# VoxPopuli.net
KiCad netlist of a schematic drawn in Altium Designer
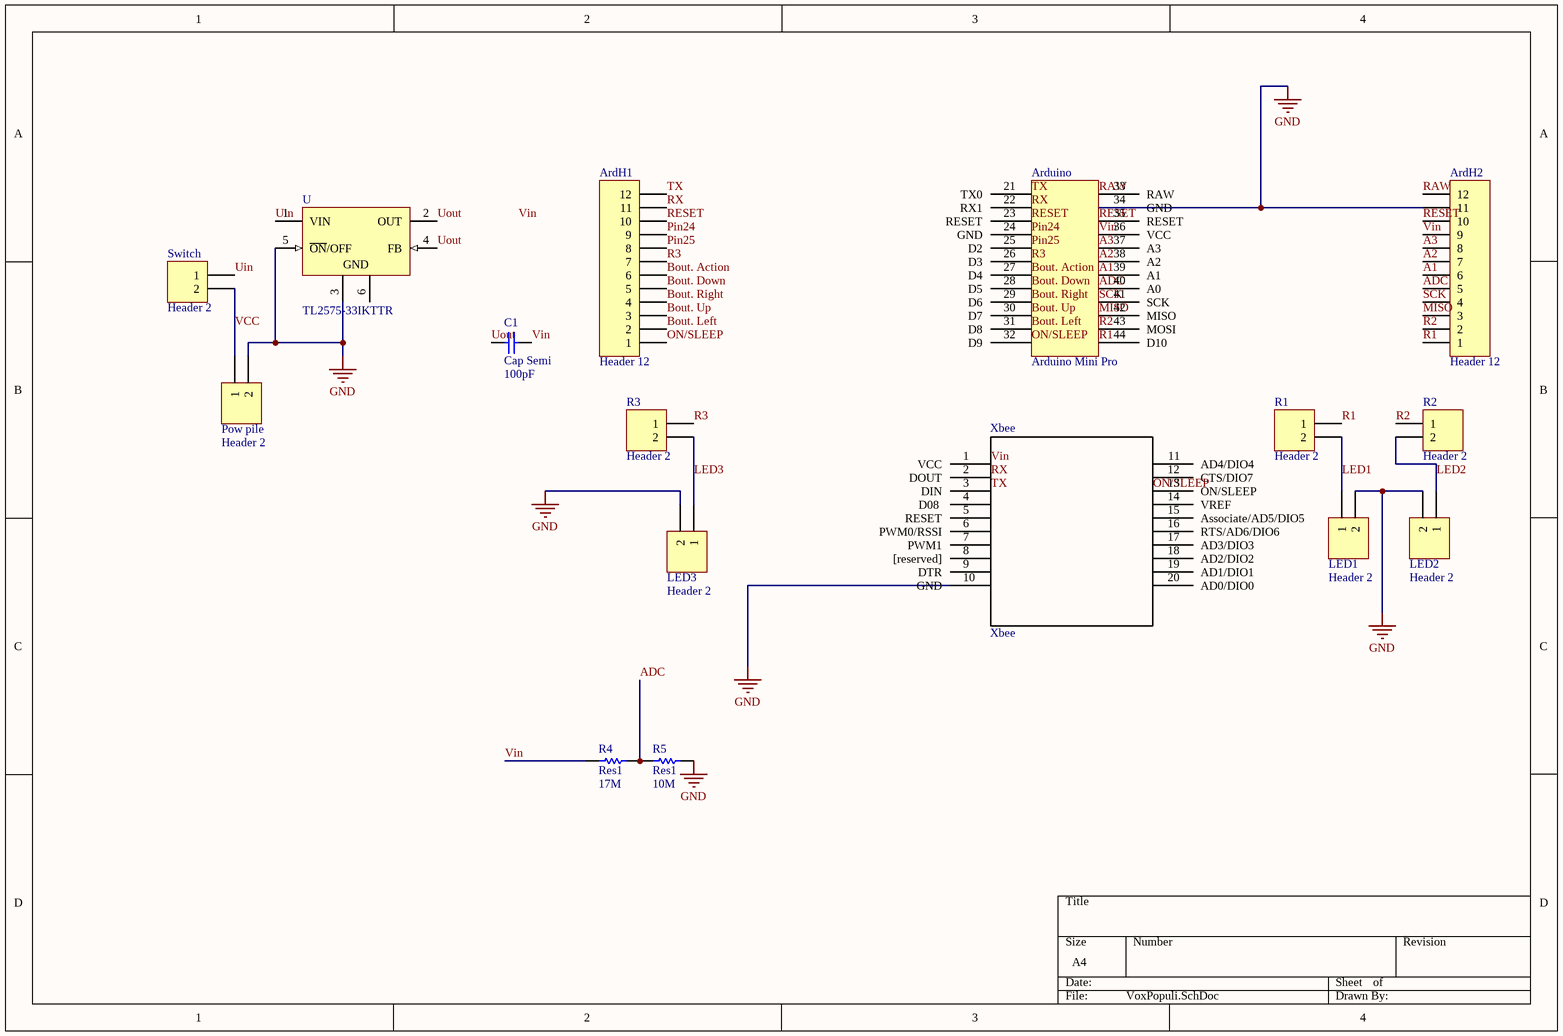
[diagram p0: VoxPopuli.SchDoc]

(export (version "E")
  (design (tool "Eeschema 10.0.6"))
  (components
    (comp (ref "ArdH1")
      (value "Header 12")
      (footprint "HEADER 12")
      (description "Header, 12-Pin")
      (fields (field (name "PUBLISHER") "Altium Limited"))
      (libsource (lib "") (part "Header 12_1"))
    )
    (comp (ref "ArdH2")
      (value "Header 12")
      (footprint "HEADER 12")
      (description "Header, 12-Pin")
      (fields (field (name "PUBLISHER") "Altium Limited"))
      (libsource (lib "Miscellaneous Connectors") (part "Header 12"))
    )
    (comp (ref "Arduino")
      (value "Arduino Mini Pro")
      (footprint "ARDUINO DIP 2")
      (description "Arduino Board")
      (libsource (lib "VoxPopuli") (part "Arduino Mini Pro"))
    )
    (comp (ref "C1")
      (value "Cap Semi")
      (footprint "C1206")
      (description "Capacitor (Semiconductor SIM Model)")
      (fields (field (name "ALTIUM_VALUE") "100pF") (field (name "PUBLISHER") "Altium Limited"))
      (libsource (lib "Miscellaneous Devices") (part "Cap Semi"))
    )
    (comp (ref "LED1")
      (value "Header 2")
      (footprint "HEADER 2")
      (description "Header, 2-Pin")
      (fields (field (name "PUBLISHER") "Altium Limited"))
      (libsource (lib "") (part "Header 2_1"))
    )
    (comp (ref "LED2")
      (value "Header 2")
      (footprint "HEADER 2")
      (description "Header, 2-Pin")
      (fields (field (name "PUBLISHER") "Altium Limited"))
      (libsource (lib "Miscellaneous Connectors") (part "Header 2"))
    )
    (comp (ref "LED3")
      (value "Header 2")
      (footprint "HEADER 2")
      (description "Header, 2-Pin")
      (fields (field (name "PUBLISHER") "Altium Limited"))
      (libsource (lib "Miscellaneous Connectors") (part "Header 2"))
    )
    (comp (ref "Pow pile")
      (value "Header 2")
      (footprint "HEADER 2")
      (description "Header, 2-Pin")
      (fields (field (name "PUBLISHER") "Altium Limited"))
      (libsource (lib "") (part "Header 2_1"))
    )
    (comp (ref "R1")
      (value "Header 2")
      (footprint "HEADER 2")
      (description "Header, 2-Pin")
      (fields (field (name "PUBLISHER") "Altium Limited"))
      (libsource (lib "Miscellaneous Connectors") (part "Header 2"))
    )
    (comp (ref "R2")
      (value "Header 2")
      (footprint "HEADER 2")
      (description "Header, 2-Pin")
      (fields (field (name "PUBLISHER") "Altium Limited"))
      (libsource (lib "") (part "Header 2_2"))
    )
    (comp (ref "R3")
      (value "Header 2")
      (footprint "HEADER 2")
      (description "Header, 2-Pin")
      (fields (field (name "PUBLISHER") "Altium Limited"))
      (libsource (lib "Miscellaneous Connectors") (part "Header 2"))
    )
    (comp (ref "R4")
      (value "Res1")
      (footprint "C1206")
      (description "Resistor")
      (fields (field (name "ALTIUM_VALUE") "17M") (field (name "PUBLISHER") "Altium Limited"))
      (libsource (lib "Miscellaneous Devices") (part "Res1"))
    )
    (comp (ref "R5")
      (value "Res1")
      (footprint "C1206")
      (description "Resistor")
      (fields (field (name "ALTIUM_VALUE") "10M") (field (name "PUBLISHER") "Altium Limited"))
      (libsource (lib "Miscellaneous Devices") (part "Res1"))
    )
    (comp (ref "Switch")
      (value "Header 2")
      (footprint "HEADER 2")
      (description "Header, 2-Pin")
      (fields (field (name "PUBLISHER") "Altium Limited"))
      (libsource (lib "Miscellaneous Connectors") (part "Header 2"))
    )
    (comp (ref "U")
      (value "TL2575-33IKTTR")
      (footprint "KTT5_N")
      (fields (field (name "MANUFACTURER") "Texas Instruments"))
      (libsource (lib "TI Power Management Step-Down Regulator") (part "TL2575-33IKTTR"))
    )
    (comp (ref "Xbee")
      (value "Xbee")
      (footprint "XBEE DIP 2")
      (description "Xbee Card")
      (libsource (lib "VoxPopuli") (part "Xbee"))
    )
  )
  (nets
    (net (code "1") (name "/A1") (class "Default")
      (node (ref "ArdH2") (pin "6") (pinfunction "6_6") (pintype "passive"))
      (node (ref "Arduino") (pin "39") (pinfunction "A1_39") (pintype "passive"))
    )
    (net (code "2") (name "/A2") (class "Default")
      (node (ref "ArdH2") (pin "7") (pinfunction "7_7") (pintype "passive"))
      (node (ref "Arduino") (pin "38") (pinfunction "A2_38") (pintype "passive"))
    )
    (net (code "3") (name "/A3") (class "Default")
      (node (ref "ArdH2") (pin "8") (pinfunction "8_8") (pintype "passive"))
      (node (ref "Arduino") (pin "37") (pinfunction "A3_37") (pintype "passive"))
    )
    (net (code "4") (name "/ADC") (class "Default")
      (node (ref "ArdH2") (pin "5") (pinfunction "5_5") (pintype "passive"))
      (node (ref "Arduino") (pin "40") (pinfunction "A0_40") (pintype "passive"))
      (node (ref "R4") (pin "2") (pinfunction "2_2") (pintype "passive"))
      (node (ref "R5") (pin "1") (pinfunction "1_1") (pintype "passive"))
    )
    (net (code "5") (name "/Bout. Action") (class "Default")
      (node (ref "ArdH1") (pin "6") (pinfunction "6_6") (pintype "passive"))
      (node (ref "Arduino") (pin "27") (pinfunction "D4_27") (pintype "passive"))
    )
    (net (code "6") (name "/Bout. Down") (class "Default")
      (node (ref "ArdH1") (pin "5") (pinfunction "5_5") (pintype "passive"))
      (node (ref "Arduino") (pin "28") (pinfunction "D5_28") (pintype "passive"))
    )
    (net (code "7") (name "/Bout. Left") (class "Default")
      (node (ref "ArdH1") (pin "2") (pinfunction "2_2") (pintype "passive"))
      (node (ref "Arduino") (pin "31") (pinfunction "D8_31") (pintype "passive"))
    )
    (net (code "8") (name "/Bout. Right") (class "Default")
      (node (ref "ArdH1") (pin "4") (pinfunction "4_4") (pintype "passive"))
      (node (ref "Arduino") (pin "29") (pinfunction "D6_29") (pintype "passive"))
    )
    (net (code "9") (name "/Bout. Up") (class "Default")
      (node (ref "ArdH1") (pin "3") (pinfunction "3_3") (pintype "passive"))
      (node (ref "Arduino") (pin "30") (pinfunction "D7_30") (pintype "passive"))
    )
    (net (code "10") (name "/LED1") (class "Default")
      (node (ref "LED1") (pin "1") (pinfunction "1_1") (pintype "passive"))
      (node (ref "R1") (pin "2") (pinfunction "2_2") (pintype "passive"))
    )
    (net (code "11") (name "/LED2") (class "Default")
      (node (ref "LED2") (pin "1") (pinfunction "1_1") (pintype "passive"))
      (node (ref "R2") (pin "2") (pinfunction "2_2") (pintype "passive"))
    )
    (net (code "12") (name "/LED3") (class "Default")
      (node (ref "LED3") (pin "1") (pinfunction "1_1") (pintype "passive"))
      (node (ref "R3") (pin "2") (pinfunction "2_2") (pintype "passive"))
    )
    (net (code "13") (name "/MISO") (class "Default")
      (node (ref "ArdH2") (pin "3") (pinfunction "3_3") (pintype "passive"))
      (node (ref "Arduino") (pin "42") (pinfunction "MISO_42") (pintype "passive"))
    )
    (net (code "14") (name "/ON{slash}SLEEP") (class "Default")
      (node (ref "ArdH1") (pin "1") (pinfunction "1_1") (pintype "passive"))
      (node (ref "Arduino") (pin "32") (pinfunction "D9_32") (pintype "passive"))
      (node (ref "Xbee") (pin "13") (pinfunction "ON/SLEEP_13") (pintype "passive"))
    )
    (net (code "15") (name "/Pin24") (class "Default")
      (node (ref "ArdH1") (pin "9") (pinfunction "9_9") (pintype "passive"))
      (node (ref "Arduino") (pin "24") (pinfunction "GND_24") (pintype "passive"))
    )
    (net (code "16") (name "/Pin25") (class "Default")
      (node (ref "ArdH1") (pin "8") (pinfunction "8_8") (pintype "passive"))
      (node (ref "Arduino") (pin "25") (pinfunction "D2_25") (pintype "passive"))
    )
    (net (code "17") (name "/R1") (class "Default")
      (node (ref "ArdH2") (pin "1") (pinfunction "1_1") (pintype "passive"))
      (node (ref "Arduino") (pin "44") (pinfunction "D10_44") (pintype "passive"))
      (node (ref "R1") (pin "1") (pinfunction "1_1") (pintype "passive"))
    )
    (net (code "18") (name "/R2") (class "Default")
      (node (ref "ArdH2") (pin "2") (pinfunction "2_2") (pintype "passive"))
      (node (ref "Arduino") (pin "43") (pinfunction "MOSI_43") (pintype "passive"))
      (node (ref "R2") (pin "1") (pinfunction "1_1") (pintype "passive"))
    )
    (net (code "19") (name "/R3") (class "Default")
      (node (ref "ArdH1") (pin "7") (pinfunction "7_7") (pintype "passive"))
      (node (ref "Arduino") (pin "26") (pinfunction "D3_26") (pintype "passive"))
      (node (ref "R3") (pin "1") (pinfunction "1_1") (pintype "passive"))
    )
    (net (code "20") (name "/RAW") (class "Default")
      (node (ref "ArdH2") (pin "12") (pinfunction "12_12") (pintype "passive"))
      (node (ref "Arduino") (pin "33") (pinfunction "RAW_33") (pintype "passive"))
    )
    (net (code "21") (name "/RESET") (class "Default")
      (node (ref "ArdH1") (pin "10") (pinfunction "10_10") (pintype "passive"))
      (node (ref "ArdH2") (pin "10") (pinfunction "10_10") (pintype "passive"))
      (node (ref "Arduino") (pin "23") (pinfunction "RESET_23") (pintype "passive"))
      (node (ref "Arduino") (pin "35") (pinfunction "RESET_35") (pintype "passive"))
    )
    (net (code "22") (name "/RX") (class "Default")
      (node (ref "ArdH1") (pin "11") (pinfunction "11_11") (pintype "passive"))
      (node (ref "Arduino") (pin "22") (pinfunction "RX1_22") (pintype "passive"))
      (node (ref "Xbee") (pin "2") (pinfunction "DOUT_2") (pintype "passive"))
    )
    (net (code "23") (name "/SCK") (class "Default")
      (node (ref "ArdH2") (pin "4") (pinfunction "4_4") (pintype "passive"))
      (node (ref "Arduino") (pin "41") (pinfunction "SCK_41") (pintype "passive"))
    )
    (net (code "24") (name "/TX") (class "Default")
      (node (ref "ArdH1") (pin "12") (pinfunction "12_12") (pintype "passive"))
      (node (ref "Arduino") (pin "21") (pinfunction "TX0_21") (pintype "passive"))
      (node (ref "Xbee") (pin "3") (pinfunction "DIN_3") (pintype "passive"))
    )
    (net (code "25") (name "/Uin") (class "Default")
      (node (ref "Switch") (pin "1") (pinfunction "1_1") (pintype "passive"))
      (node (ref "U") (pin "1") (pinfunction "VIN_1") (pintype "power_in"))
    )
    (net (code "26") (name "/Uout") (class "Default")
      (node (ref "C1") (pin "1") (pinfunction "1_1") (pintype "passive"))
      (node (ref "U") (pin "2") (pinfunction "OUT_2") (pintype "power_in"))
      (node (ref "U") (pin "4") (pinfunction "FB_4") (pintype "input"))
    )
    (net (code "27") (name "/VCC") (class "Default")
      (node (ref "Pow pile") (pin "1") (pinfunction "1_1") (pintype "passive"))
      (node (ref "Switch") (pin "2") (pinfunction "2_2") (pintype "passive"))
    )
    (net (code "28") (name "/Vin") (class "Default")
      (node (ref "ArdH2") (pin "9") (pinfunction "9_9") (pintype "passive"))
      (node (ref "Arduino") (pin "36") (pinfunction "VCC_36") (pintype "passive"))
      (node (ref "C1") (pin "2") (pinfunction "2_2") (pintype "passive"))
      (node (ref "R4") (pin "1") (pinfunction "1_1") (pintype "passive"))
      (node (ref "Xbee") (pin "1") (pinfunction "VCC_1") (pintype "passive"))
    )
    (net (code "29") (name "GND") (class "Default")
      (node (ref "ArdH2") (pin "11") (pinfunction "11_11") (pintype "passive"))
      (node (ref "Arduino") (pin "34") (pinfunction "GND_34") (pintype "passive"))
      (node (ref "LED1") (pin "2") (pinfunction "2_2") (pintype "passive"))
      (node (ref "LED2") (pin "2") (pinfunction "2_2") (pintype "passive"))
      (node (ref "LED3") (pin "2") (pinfunction "2_2") (pintype "passive"))
      (node (ref "Pow pile") (pin "2") (pinfunction "2_2") (pintype "passive"))
      (node (ref "R5") (pin "2") (pinfunction "2_2") (pintype "passive"))
      (node (ref "U") (pin "3") (pinfunction "GND_3") (pintype "power_in"))
      (node (ref "U") (pin "5") (pinfunction "~{ON}/OFF_5") (pintype "input"))
      (node (ref "Xbee") (pin "10") (pinfunction "GND_10") (pintype "passive"))
    )
    (net (code "30") (name "unconnected-(U-GND-Pad6)") (class "Default")
      (node (ref "U") (pin "6") (pinfunction "GND_6") (pintype "power_in"))
    )
    (net (code "31") (name "unconnected-(Xbee-AD0{slash}DIO0-Pad20)") (class "Default")
      (node (ref "Xbee") (pin "20") (pinfunction "AD0/DIO0_20") (pintype "passive"))
    )
    (net (code "32") (name "unconnected-(Xbee-AD1{slash}DIO1-Pad19)") (class "Default")
      (node (ref "Xbee") (pin "19") (pinfunction "AD1/DIO1_19") (pintype "passive"))
    )
    (net (code "33") (name "unconnected-(Xbee-AD2{slash}DIO2-Pad18)") (class "Default")
      (node (ref "Xbee") (pin "18") (pinfunction "AD2/DIO2_18") (pintype "passive"))
    )
    (net (code "34") (name "unconnected-(Xbee-AD3{slash}DIO3-Pad17)") (class "Default")
      (node (ref "Xbee") (pin "17") (pinfunction "AD3/DIO3_17") (pintype "passive"))
    )
    (net (code "35") (name "unconnected-(Xbee-AD4{slash}DIO4-Pad11)") (class "Default")
      (node (ref "Xbee") (pin "11") (pinfunction "AD4/DIO4_11") (pintype "passive"))
    )
    (net (code "36") (name "unconnected-(Xbee-Associate{slash}AD5{slash}DIO5-Pad15)") (class "Default")
      (node (ref "Xbee") (pin "15") (pinfunction "Associate/AD5/DIO5_15") (pintype "passive"))
    )
    (net (code "37") (name "unconnected-(Xbee-CTS{slash}DIO7-Pad12)") (class "Default")
      (node (ref "Xbee") (pin "12") (pinfunction "CTS/DIO7_12") (pintype "passive"))
    )
    (net (code "38") (name "unconnected-(Xbee-D08-Pad4)") (class "Default")
      (node (ref "Xbee") (pin "4") (pinfunction "D08_4") (pintype "passive"))
    )
    (net (code "39") (name "unconnected-(Xbee-DTR-Pad9)") (class "Default")
      (node (ref "Xbee") (pin "9") (pinfunction "DTR_9") (pintype "passive"))
    )
    (net (code "40") (name "unconnected-(Xbee-PWM0{slash}RSSI-Pad6)") (class "Default")
      (node (ref "Xbee") (pin "6") (pinfunction "PWM0/RSSI_6") (pintype "passive"))
    )
    (net (code "41") (name "unconnected-(Xbee-PWM1-Pad7)") (class "Default")
      (node (ref "Xbee") (pin "7") (pinfunction "PWM1_7") (pintype "passive"))
    )
    (net (code "42") (name "unconnected-(Xbee-RESET-Pad5)") (class "Default")
      (node (ref "Xbee") (pin "5") (pinfunction "RESET_5") (pintype "passive"))
    )
    (net (code "43") (name "unconnected-(Xbee-RTS{slash}AD6{slash}DIO6-Pad16)") (class "Default")
      (node (ref "Xbee") (pin "16") (pinfunction "RTS/AD6/DIO6_16") (pintype "passive"))
    )
    (net (code "44") (name "unconnected-(Xbee-VREF-Pad14)") (class "Default")
      (node (ref "Xbee") (pin "14") (pinfunction "VREF_14") (pintype "passive"))
    )
    (net (code "45") (name "unconnected-(Xbee-[reserved]-Pad8)") (class "Default")
      (node (ref "Xbee") (pin "8") (pinfunction "[reserved]_8") (pintype "passive"))
    )
  )
)
